# RASPBERRY_PI_PICO.net
KiCad netlist of a schematic drawn in Altium Designer
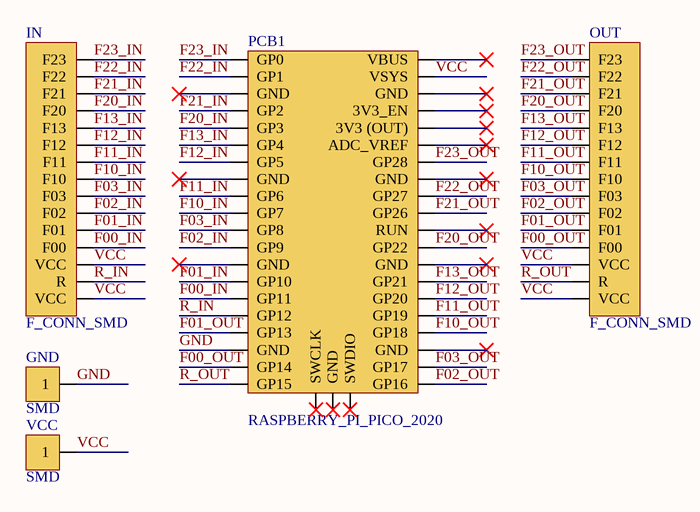
[diagram p0: RASPBERRY_PI_PICO.SchDoc]

(export (version "E")
  (design (tool "Eeschema 10.0.6"))
  (components
    (comp (ref "GND") (value "SMD") (footprint "SMD_PAD") (libsource (lib "Schlib_DW") (part "SMD_PAD")))
    (comp (ref "IN")
      (value "F_CONN_SMD")
      (footprint "F_CONNECTOR_SMD")
      (libsource (lib "") (part "F_CONNECTOR_SMD_1"))
    )
    (comp (ref "OUT")
      (value "F_CONN_SMD")
      (footprint "F_CONNECTOR_SMD")
      (libsource (lib "Schlib_DW") (part "F_CONNECTOR_SMD"))
    )
    (comp (ref "PCB1")
      (value "RASPBERRY_PI_PICO_2020")
      (footprint "RASPBERRY_PI_PICO_2020\\")
      (libsource (lib "Schlib_DW") (part "RASPBERRY_PI_PICO_2020"))
    )
    (comp (ref "VCC") (value "SMD") (footprint "SMD_PAD") (libsource (lib "Schlib_DW") (part "SMD_PAD")))
  )
  (nets
    (net (code "1") (name "/F00_IN") (class "Default")
      (node (ref "IN") (pin "12") (pinfunction "F00_12") (pintype "passive"))
      (node (ref "PCB1") (pin "15") (pinfunction "GP11_15") (pintype "passive"))
    )
    (net (code "2") (name "/F00_OUT") (class "Default")
      (node (ref "OUT") (pin "12") (pinfunction "F00_12") (pintype "passive"))
      (node (ref "PCB1") (pin "19") (pinfunction "GP14_19") (pintype "passive"))
    )
    (net (code "3") (name "/F01_IN") (class "Default")
      (node (ref "IN") (pin "11") (pinfunction "F01_11") (pintype "passive"))
      (node (ref "PCB1") (pin "14") (pinfunction "GP10_14") (pintype "passive"))
    )
    (net (code "4") (name "/F01_OUT") (class "Default")
      (node (ref "OUT") (pin "11") (pinfunction "F01_11") (pintype "passive"))
      (node (ref "PCB1") (pin "17") (pinfunction "GP13_17") (pintype "passive"))
    )
    (net (code "5") (name "/F02_IN") (class "Default")
      (node (ref "IN") (pin "10") (pinfunction "F02_10") (pintype "passive"))
      (node (ref "PCB1") (pin "12") (pinfunction "GP9_12") (pintype "passive"))
    )
    (net (code "6") (name "/F02_OUT") (class "Default")
      (node (ref "OUT") (pin "10") (pinfunction "F02_10") (pintype "passive"))
      (node (ref "PCB1") (pin "24") (pinfunction "GP16_24") (pintype "passive"))
    )
    (net (code "7") (name "/F03_IN") (class "Default")
      (node (ref "IN") (pin "9") (pinfunction "F03_9") (pintype "passive"))
      (node (ref "PCB1") (pin "11") (pinfunction "GP8_11") (pintype "passive"))
    )
    (net (code "8") (name "/F03_OUT") (class "Default")
      (node (ref "OUT") (pin "9") (pinfunction "F03_9") (pintype "passive"))
      (node (ref "PCB1") (pin "25") (pinfunction "GP17_25") (pintype "passive"))
    )
    (net (code "9") (name "/F10_IN") (class "Default")
      (node (ref "IN") (pin "8") (pinfunction "F10_8") (pintype "passive"))
      (node (ref "PCB1") (pin "10") (pinfunction "GP7_10") (pintype "passive"))
    )
    (net (code "10") (name "/F10_OUT") (class "Default")
      (node (ref "OUT") (pin "8") (pinfunction "F10_8") (pintype "passive"))
      (node (ref "PCB1") (pin "27") (pinfunction "GP18_27") (pintype "passive"))
    )
    (net (code "11") (name "/F11_IN") (class "Default")
      (node (ref "IN") (pin "7") (pinfunction "F11_7") (pintype "passive"))
      (node (ref "PCB1") (pin "9") (pinfunction "GP6_9") (pintype "passive"))
    )
    (net (code "12") (name "/F11_OUT") (class "Default")
      (node (ref "OUT") (pin "7") (pinfunction "F11_7") (pintype "passive"))
      (node (ref "PCB1") (pin "28") (pinfunction "GP19_28") (pintype "passive"))
    )
    (net (code "13") (name "/F12_IN") (class "Default")
      (node (ref "IN") (pin "6") (pinfunction "F12_6") (pintype "passive"))
      (node (ref "PCB1") (pin "7") (pinfunction "GP5_7") (pintype "passive"))
    )
    (net (code "14") (name "/F12_OUT") (class "Default")
      (node (ref "OUT") (pin "6") (pinfunction "F12_6") (pintype "passive"))
      (node (ref "PCB1") (pin "29") (pinfunction "GP20_29") (pintype "passive"))
    )
    (net (code "15") (name "/F13_IN") (class "Default")
      (node (ref "IN") (pin "5") (pinfunction "F13_5") (pintype "passive"))
      (node (ref "PCB1") (pin "6") (pinfunction "GP4_6") (pintype "passive"))
    )
    (net (code "16") (name "/F13_OUT") (class "Default")
      (node (ref "OUT") (pin "5") (pinfunction "F13_5") (pintype "passive"))
      (node (ref "PCB1") (pin "30") (pinfunction "GP21_30") (pintype "passive"))
    )
    (net (code "17") (name "/F20_IN") (class "Default")
      (node (ref "IN") (pin "4") (pinfunction "F20_4") (pintype "passive"))
      (node (ref "PCB1") (pin "5") (pinfunction "GP3_5") (pintype "passive"))
    )
    (net (code "18") (name "/F20_OUT") (class "Default")
      (node (ref "OUT") (pin "4") (pinfunction "F20_4") (pintype "passive"))
      (node (ref "PCB1") (pin "32") (pinfunction "GP22_32") (pintype "passive"))
    )
    (net (code "19") (name "/F21_IN") (class "Default")
      (node (ref "IN") (pin "3") (pinfunction "F21_3") (pintype "passive"))
      (node (ref "PCB1") (pin "4") (pinfunction "GP2_4") (pintype "passive"))
    )
    (net (code "20") (name "/F21_OUT") (class "Default")
      (node (ref "OUT") (pin "3") (pinfunction "F21_3") (pintype "passive"))
      (node (ref "PCB1") (pin "34") (pinfunction "GP26_34") (pintype "passive"))
    )
    (net (code "21") (name "/F22_IN") (class "Default")
      (node (ref "IN") (pin "2") (pinfunction "F22_2") (pintype "passive"))
      (node (ref "PCB1") (pin "2") (pinfunction "GP1_2") (pintype "passive"))
    )
    (net (code "22") (name "/F22_OUT") (class "Default")
      (node (ref "OUT") (pin "2") (pinfunction "F22_2") (pintype "passive"))
      (node (ref "PCB1") (pin "35") (pinfunction "GP27_35") (pintype "passive"))
    )
    (net (code "23") (name "/F23_IN") (class "Default")
      (node (ref "IN") (pin "1") (pinfunction "F23_1") (pintype "passive"))
      (node (ref "PCB1") (pin "1") (pinfunction "GP0_1") (pintype "passive"))
    )
    (net (code "24") (name "/F23_OUT") (class "Default")
      (node (ref "OUT") (pin "1") (pinfunction "F23_1") (pintype "passive"))
      (node (ref "PCB1") (pin "37") (pinfunction "GP28_37") (pintype "passive"))
    )
    (net (code "25") (name "/GND") (class "Default")
      (node (ref "GND") (pin "1") (pinfunction "1_1") (pintype "passive"))
      (node (ref "PCB1") (pin "18") (pinfunction "GND_18") (pintype "passive"))
    )
    (net (code "26") (name "/R_IN") (class "Default")
      (node (ref "IN") (pin "14") (pinfunction "R_14") (pintype "passive"))
      (node (ref "PCB1") (pin "16") (pinfunction "GP12_16") (pintype "passive"))
    )
    (net (code "27") (name "/R_OUT") (class "Default")
      (node (ref "OUT") (pin "14") (pinfunction "R_14") (pintype "passive"))
      (node (ref "PCB1") (pin "20") (pinfunction "GP15_20") (pintype "passive"))
    )
    (net (code "28") (name "/VCC") (class "Default")
      (node (ref "IN") (pin "13") (pinfunction "VCC_13") (pintype "passive"))
      (node (ref "IN") (pin "15") (pinfunction "VCC_15") (pintype "passive"))
      (node (ref "OUT") (pin "13") (pinfunction "VCC_13") (pintype "passive"))
      (node (ref "OUT") (pin "15") (pinfunction "VCC_15") (pintype "passive"))
      (node (ref "PCB1") (pin "42") (pinfunction "VSYS_42") (pintype "passive"))
      (node (ref "VCC") (pin "1") (pinfunction "1_1") (pintype "passive"))
    )
    (net (code "29") (name "unconnected-(PCB1-3V3_(OUT)-Pad39)") (class "Default")
      (node (ref "PCB1") (pin "39") (pinfunction "3V3_(OUT)_39") (pintype "passive+no_connect"))
    )
    (net (code "30") (name "unconnected-(PCB1-3V3_EN-Pad40)") (class "Default")
      (node (ref "PCB1") (pin "40") (pinfunction "3V3_EN_40") (pintype "passive+no_connect"))
    )
    (net (code "31") (name "unconnected-(PCB1-ADC_VREF-Pad38)") (class "Default")
      (node (ref "PCB1") (pin "38") (pinfunction "ADC_VREF_38") (pintype "passive+no_connect"))
    )
    (net (code "32") (name "unconnected-(PCB1-GND-Pad3)") (class "Default")
      (node (ref "PCB1") (pin "3") (pinfunction "GND_3") (pintype "passive+no_connect"))
    )
    (net (code "33") (name "unconnected-(PCB1-GND-Pad8)") (class "Default")
      (node (ref "PCB1") (pin "8") (pinfunction "GND_8") (pintype "passive+no_connect"))
    )
    (net (code "34") (name "unconnected-(PCB1-GND-Pad13)") (class "Default")
      (node (ref "PCB1") (pin "13") (pinfunction "GND_13") (pintype "passive+no_connect"))
    )
    (net (code "35") (name "unconnected-(PCB1-GND-Pad22)") (class "Default")
      (node (ref "PCB1") (pin "22") (pinfunction "GND_22") (pintype "passive+no_connect"))
    )
    (net (code "36") (name "unconnected-(PCB1-GND-Pad26)") (class "Default")
      (node (ref "PCB1") (pin "26") (pinfunction "GND_26") (pintype "passive+no_connect"))
    )
    (net (code "37") (name "unconnected-(PCB1-GND-Pad31)") (class "Default")
      (node (ref "PCB1") (pin "31") (pinfunction "GND_31") (pintype "passive+no_connect"))
    )
    (net (code "38") (name "unconnected-(PCB1-GND-Pad36)") (class "Default")
      (node (ref "PCB1") (pin "36") (pinfunction "GND_36") (pintype "passive+no_connect"))
    )
    (net (code "39") (name "unconnected-(PCB1-GND-Pad41)") (class "Default")
      (node (ref "PCB1") (pin "41") (pinfunction "GND_41") (pintype "passive+no_connect"))
    )
    (net (code "40") (name "unconnected-(PCB1-RUN-Pad33)") (class "Default")
      (node (ref "PCB1") (pin "33") (pinfunction "RUN_33") (pintype "passive+no_connect"))
    )
    (net (code "41") (name "unconnected-(PCB1-SWCLK-Pad21)") (class "Default")
      (node (ref "PCB1") (pin "21") (pinfunction "SWCLK_21") (pintype "passive+no_connect"))
    )
    (net (code "42") (name "unconnected-(PCB1-SWDIO-Pad23)") (class "Default")
      (node (ref "PCB1") (pin "23") (pinfunction "SWDIO_23") (pintype "passive+no_connect"))
    )
    (net (code "43") (name "unconnected-(PCB1-VBUS-Pad43)") (class "Default")
      (node (ref "PCB1") (pin "43") (pinfunction "VBUS_43") (pintype "passive+no_connect"))
    )
  )
)
